# CAN_Breakout_3_0.net
KiCad netlist of a schematic drawn in EAGLE
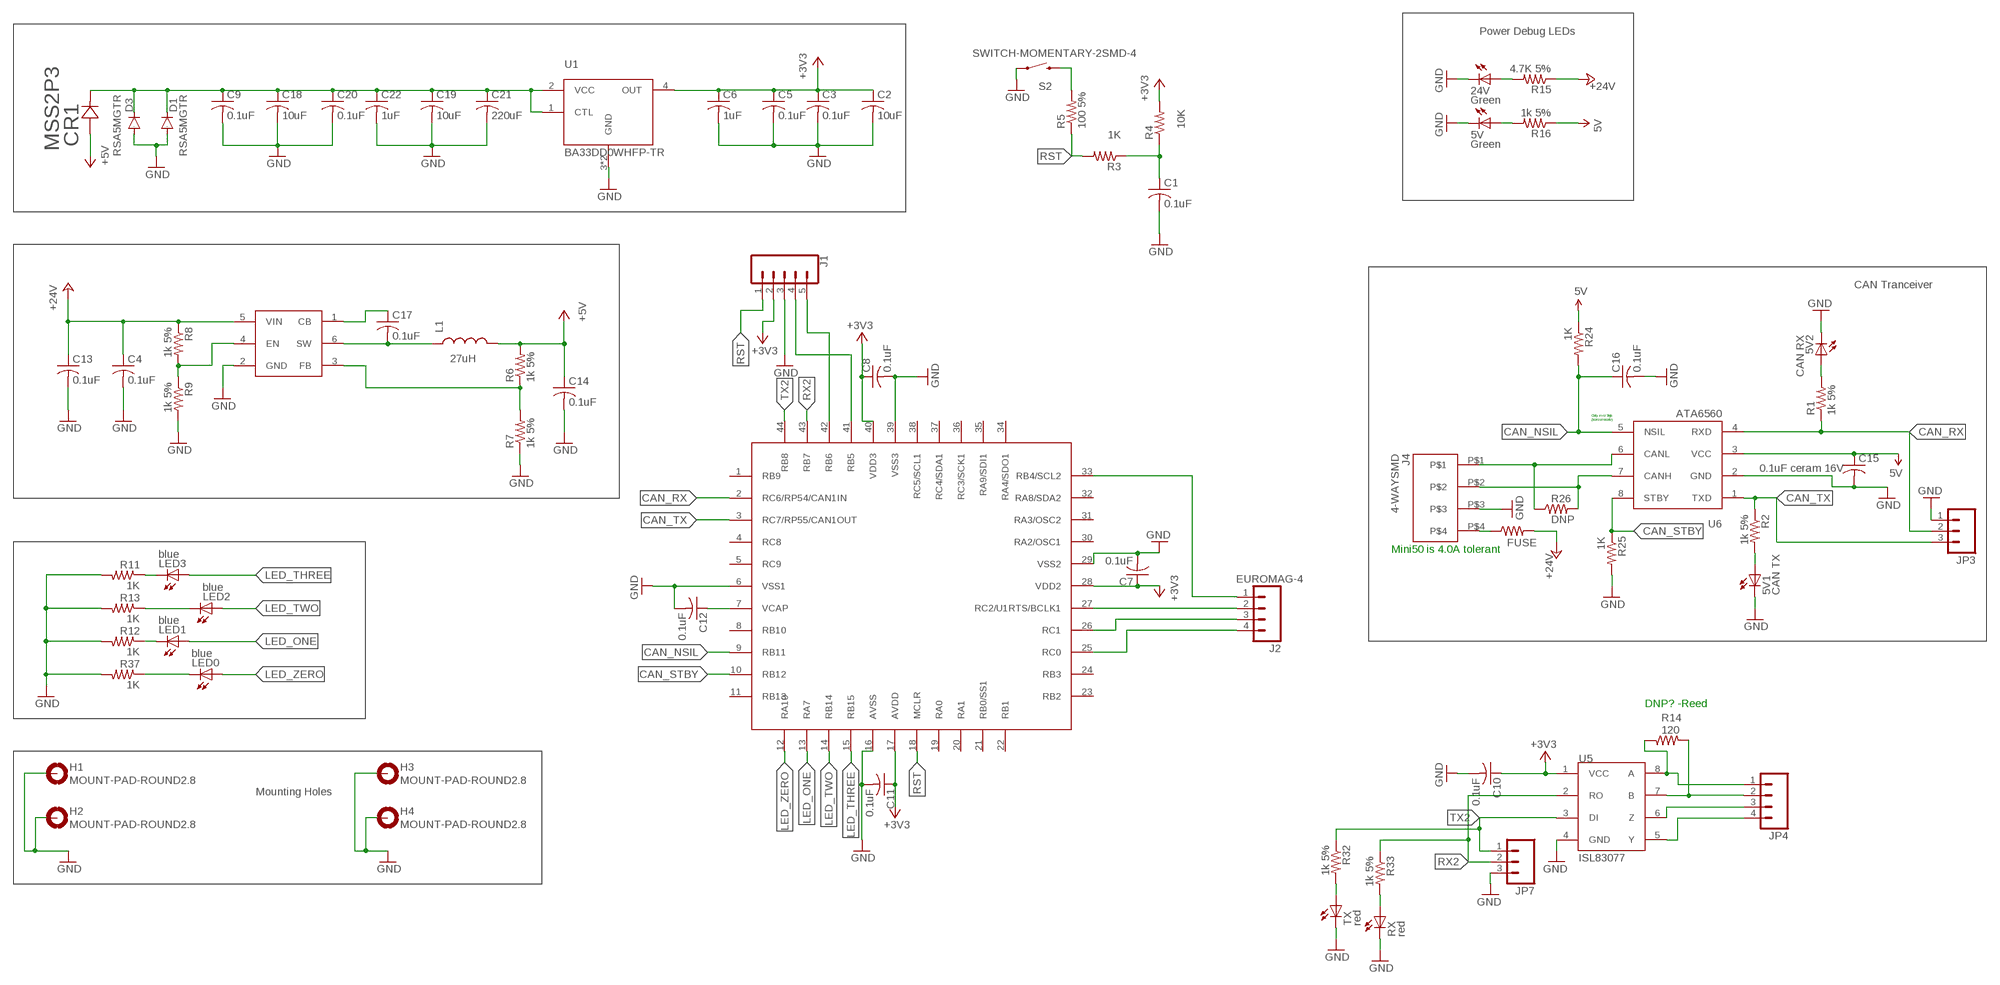
[diagram p0: schematic, sheet 1]

(export (version "E")
  (design (tool "Eeschema 10.0.6"))
  (components
    (comp (ref "5V")
      (value "Green")
      (footprint "eagle-import:CHIP-LED0805")
      (libsource (lib "eagle-import") (part "LEDCHIP-LED0805"))
    )
    (comp (ref "5V1")
      (value "CAN TX")
      (footprint "eagle-import:CHIP-LED0805")
      (libsource (lib "eagle-import") (part "LEDCHIP-LED0805"))
    )
    (comp (ref "5V2")
      (value "CAN RX")
      (footprint "eagle-import:CHIP-LED0805")
      (libsource (lib "eagle-import") (part "LEDCHIP-LED0805"))
    )
    (comp (ref "24V")
      (value "Green")
      (footprint "eagle-import:CHIP-LED0805")
      (libsource (lib "eagle-import") (part "LEDCHIP-LED0805"))
    )
    (comp (ref "C1")
      (value "0.1uF")
      (footprint "eagle-import:C0805")
      (libsource (lib "eagle-import") (part "C-USC0805"))
    )
    (comp (ref "C2")
      (value "10uF")
      (footprint "eagle-import:C0805")
      (libsource (lib "eagle-import") (part "C-USC0805"))
    )
    (comp (ref "C3")
      (value "0.1uF")
      (footprint "eagle-import:C0805")
      (libsource (lib "eagle-import") (part "C-USC0805"))
    )
    (comp (ref "C4")
      (value "0.1uF")
      (footprint "eagle-import:C0805")
      (libsource (lib "eagle-import") (part "C-USC0805"))
    )
    (comp (ref "C5")
      (value "0.1uF")
      (footprint "eagle-import:C0805")
      (libsource (lib "eagle-import") (part "C-USC0805"))
    )
    (comp (ref "C6")
      (value "1uF")
      (footprint "eagle-import:C0805")
      (libsource (lib "eagle-import") (part "C-USC0805"))
    )
    (comp (ref "C7")
      (value "0.1uF")
      (footprint "eagle-import:C0805")
      (libsource (lib "eagle-import") (part "C-USC0805"))
    )
    (comp (ref "C8")
      (value "0.1uF")
      (footprint "eagle-import:C0805")
      (libsource (lib "eagle-import") (part "C-USC0805"))
    )
    (comp (ref "C9")
      (value "0.1uF")
      (footprint "eagle-import:C0805")
      (libsource (lib "eagle-import") (part "C-USC0805"))
    )
    (comp (ref "C10")
      (value "0.1uF")
      (footprint "eagle-import:C0805")
      (libsource (lib "eagle-import") (part "C-USC0805"))
    )
    (comp (ref "C11")
      (value "0.1uF")
      (footprint "eagle-import:C0805")
      (libsource (lib "eagle-import") (part "C-USC0805"))
    )
    (comp (ref "C12")
      (value "0.1uF")
      (footprint "eagle-import:C0805")
      (libsource (lib "eagle-import") (part "C-USC0805"))
    )
    (comp (ref "C13")
      (value "0.1uF")
      (footprint "eagle-import:C0805")
      (libsource (lib "eagle-import") (part "C-USC0805"))
    )
    (comp (ref "C14")
      (value "0.1uF")
      (footprint "eagle-import:C0805")
      (libsource (lib "eagle-import") (part "C-USC0805"))
    )
    (comp (ref "C15")
      (value "0.1uF ceram 16V")
      (footprint "eagle-import:C0805")
      (libsource (lib "eagle-import") (part "C-USC0805"))
    )
    (comp (ref "C16")
      (value "0.1uF")
      (footprint "eagle-import:C0805")
      (libsource (lib "eagle-import") (part "C-USC0805"))
    )
    (comp (ref "C17")
      (value "0.1uF")
      (footprint "eagle-import:C0805")
      (libsource (lib "eagle-import") (part "C-USC0805"))
    )
    (comp (ref "C18")
      (value "10uF")
      (footprint "eagle-import:C0805")
      (libsource (lib "eagle-import") (part "C-USC0805"))
    )
    (comp (ref "C19")
      (value "10uF")
      (footprint "eagle-import:C0805")
      (libsource (lib "eagle-import") (part "C-USC0805"))
    )
    (comp (ref "C20")
      (value "0.1uF")
      (footprint "eagle-import:C0805")
      (libsource (lib "eagle-import") (part "C-USC0805"))
    )
    (comp (ref "C21")
      (value "220uF")
      (footprint "eagle-import:C0805")
      (libsource (lib "eagle-import") (part "C-USC0805"))
    )
    (comp (ref "C22")
      (value "1uF")
      (footprint "eagle-import:C0805")
      (libsource (lib "eagle-import") (part "C-USC0805"))
    )
    (comp (ref "CR1")
      (value "MSS2P3")
      (footprint "eagle-import:DIODE_MSP3V3-L")
      (fields (field (name "MANUFACTURER_PART_NUMBER") "MSS2P3M389A"))
      (libsource (lib "eagle-import") (part "MSS2P3-M3/89ADIODE_MSP3V3-L"))
    )
    (comp (ref "D1")
      (value "RSA5MGTR")
      (footprint "eagle-import:SOD-123_MINI-SMA")
      (libsource (lib "eagle-import") (part "CGRM400-G4"))
    )
    (comp (ref "D3")
      (value "RSA5MGTR")
      (footprint "eagle-import:SOD-123_MINI-SMA")
      (libsource (lib "eagle-import") (part "CGRM400-G4"))
    )
    (comp (ref "FUSE")
      (value "RESISTOR1206")
      (footprint "eagle-import:1206")
      (libsource (lib "eagle-import") (part "RESISTOR1206"))
    )
    (comp (ref "H1")
      (value "MOUNT-PAD-ROUND2.8")
      (footprint "eagle-import:2,8-PAD")
      (libsource (lib "eagle-import") (part "MOUNT-PAD-ROUND2.8"))
    )
    (comp (ref "H2")
      (value "MOUNT-PAD-ROUND2.8")
      (footprint "eagle-import:2,8-PAD")
      (libsource (lib "eagle-import") (part "MOUNT-PAD-ROUND2.8"))
    )
    (comp (ref "H3")
      (value "MOUNT-PAD-ROUND2.8")
      (footprint "eagle-import:2,8-PAD")
      (libsource (lib "eagle-import") (part "MOUNT-PAD-ROUND2.8"))
    )
    (comp (ref "H4")
      (value "MOUNT-PAD-ROUND2.8")
      (footprint "eagle-import:2,8-PAD")
      (libsource (lib "eagle-import") (part "MOUNT-PAD-ROUND2.8"))
    )
    (comp (ref "J1")
      (value "CONN_05")
      (footprint "eagle-import:1X05")
      (libsource (lib "eagle-import") (part "CONN_05"))
    )
    (comp (ref "J2")
      (value "EUROMAG-4")
      (footprint "eagle-import:M4")
      (libsource (lib "eagle-import") (part "EUROMAG-4"))
    )
    (comp (ref "J4")
      (value "4-WAYSMD")
      (footprint "eagle-import:4-WAY-SMD-90D")
      (libsource (lib "eagle-import") (part "4-WAYSMD"))
    )
    (comp (ref "JP3")
      (value "M03LOCK")
      (footprint "eagle-import:1X03_LOCK")
      (libsource (lib "eagle-import") (part "M03LOCK"))
    )
    (comp (ref "JP4")
      (value "M04POLAR_LOCK")
      (footprint "eagle-import:MOLEX-1X4_LOCK")
      (libsource (lib "eagle-import") (part "M04POLAR_LOCK"))
    )
    (comp (ref "JP7")
      (value "M03LOCK")
      (footprint "eagle-import:1X03_LOCK")
      (libsource (lib "eagle-import") (part "M03LOCK"))
    )
    (comp (ref "L1")
      (value "27uH")
      (footprint "eagle-import:0805")
      (libsource (lib "eagle-import") (part "INDUCTOR1"))
    )
    (comp (ref "LED0")
      (value "blue")
      (footprint "eagle-import:CHIPLED_0805")
      (libsource (lib "eagle-import") (part "LEDCHIPLED_0805"))
    )
    (comp (ref "LED1")
      (value "blue")
      (footprint "eagle-import:CHIPLED_0805")
      (libsource (lib "eagle-import") (part "LEDCHIPLED_0805"))
    )
    (comp (ref "LED2")
      (value "blue")
      (footprint "eagle-import:CHIPLED_0805")
      (libsource (lib "eagle-import") (part "LEDCHIPLED_0805"))
    )
    (comp (ref "LED3")
      (value "blue")
      (footprint "eagle-import:CHIPLED_0805")
      (libsource (lib "eagle-import") (part "LEDCHIPLED_0805"))
    )
    (comp (ref "R1")
      (value "1k 5%")
      (footprint "eagle-import:M0805")
      (libsource (lib "eagle-import") (part "R-US_M0805"))
    )
    (comp (ref "R2")
      (value "1k 5%")
      (footprint "eagle-import:M0805")
      (libsource (lib "eagle-import") (part "R-US_M0805"))
    )
    (comp (ref "R3")
      (value "1K")
      (footprint "eagle-import:M0805")
      (libsource (lib "eagle-import") (part "R-US_M0805"))
    )
    (comp (ref "R4")
      (value "10K")
      (footprint "eagle-import:M0805")
      (libsource (lib "eagle-import") (part "R-US_M0805"))
    )
    (comp (ref "R5")
      (value "100 5%")
      (footprint "eagle-import:M0805")
      (libsource (lib "eagle-import") (part "R-US_M0805"))
    )
    (comp (ref "R6")
      (value "1k 5%")
      (footprint "eagle-import:M0805")
      (libsource (lib "eagle-import") (part "R-US_M0805"))
    )
    (comp (ref "R7")
      (value "1k 5%")
      (footprint "eagle-import:M0805")
      (libsource (lib "eagle-import") (part "R-US_M0805"))
    )
    (comp (ref "R8")
      (value "1k 5%")
      (footprint "eagle-import:M0805")
      (libsource (lib "eagle-import") (part "R-US_M0805"))
    )
    (comp (ref "R9")
      (value "1k 5%")
      (footprint "eagle-import:M0805")
      (libsource (lib "eagle-import") (part "R-US_M0805"))
    )
    (comp (ref "R11")
      (value "1K")
      (footprint "eagle-import:M0805")
      (libsource (lib "eagle-import") (part "R-US_M0805"))
    )
    (comp (ref "R12")
      (value "1K")
      (footprint "eagle-import:M0805")
      (libsource (lib "eagle-import") (part "R-US_M0805"))
    )
    (comp (ref "R13")
      (value "1K")
      (footprint "eagle-import:M0805")
      (libsource (lib "eagle-import") (part "R-US_M0805"))
    )
    (comp (ref "R14")
      (value "120")
      (footprint "eagle-import:M0805")
      (libsource (lib "eagle-import") (part "R-US_M0805"))
    )
    (comp (ref "R15")
      (value "4.7K 5%")
      (footprint "eagle-import:M0805")
      (libsource (lib "eagle-import") (part "R-US_M0805"))
    )
    (comp (ref "R16")
      (value "1k 5%")
      (footprint "eagle-import:M0805")
      (libsource (lib "eagle-import") (part "R-US_M0805"))
    )
    (comp (ref "R24")
      (value "1K")
      (footprint "eagle-import:M0805")
      (libsource (lib "eagle-import") (part "R-US_M0805"))
    )
    (comp (ref "R25")
      (value "1K")
      (footprint "eagle-import:M0805")
      (libsource (lib "eagle-import") (part "R-US_M0805"))
    )
    (comp (ref "R26")
      (value "DNP")
      (footprint "eagle-import:M0805")
      (libsource (lib "eagle-import") (part "R-US_M0805"))
    )
    (comp (ref "R32")
      (value "1k 5%")
      (footprint "eagle-import:M0805")
      (libsource (lib "eagle-import") (part "R-US_M0805"))
    )
    (comp (ref "R33")
      (value "1k 5%")
      (footprint "eagle-import:M0805")
      (libsource (lib "eagle-import") (part "R-US_M0805"))
    )
    (comp (ref "R37")
      (value "1K")
      (footprint "eagle-import:M0805")
      (libsource (lib "eagle-import") (part "R-US_M0805"))
    )
    (comp (ref "RX")
      (value "red")
      (footprint "eagle-import:CHIP-LED0805")
      (libsource (lib "eagle-import") (part "LEDCHIP-LED0805"))
    )
    (comp (ref "S2")
      (value "SWITCH-MOMENTARY-2SMD-4")
      (footprint "eagle-import:TACTILE_SWITCH_TALL")
      (libsource (lib "eagle-import") (part "SWITCH-MOMENTARY-2SMD-4"))
    )
    (comp (ref "TX")
      (value "red")
      (footprint "eagle-import:CHIP-LED0805")
      (libsource (lib "eagle-import") (part "LEDCHIP-LED0805"))
    )
    (comp (ref "U1")
      (value "BA33DD0WHFP-TR")
      (footprint "eagle-import:HRP5")
      (libsource (lib "eagle-import") (part "BA33DD0WHFP-TR"))
    )
    (comp (ref "U2")
      (value "DSPIC33EP512GP504")
      (footprint "eagle-import:TQFP-44")
      (libsource (lib "eagle-import") (part "DSPIC33EP512GP504"))
    )
    (comp (ref "U5")
      (value "ISL83077")
      (footprint "eagle-import:SO08")
      (libsource (lib "eagle-import") (part "ISL83077"))
    )
    (comp (ref "U6")
      (value "ATA6560")
      (footprint "eagle-import:SOIC8")
      (libsource (lib "eagle-import") (part "ATA6560"))
    )
    (comp (ref "U7")
      (value "TPS560430YDBVR")
      (footprint "eagle-import:SOT23-6")
      (libsource (lib "eagle-import") (part "TPS560430YDBVR"))
    )
  )
  (nets
    (net (code "1") (name "+3V3") (class "Default")
      (node (ref "C10") (pin "1") (pinfunction "1_1") (pintype "passive"))
      (node (ref "C11") (pin "1") (pinfunction "1_1") (pintype "passive"))
      (node (ref "C2") (pin "1") (pinfunction "1_1") (pintype "passive"))
      (node (ref "C3") (pin "1") (pinfunction "1_1") (pintype "passive"))
      (node (ref "C5") (pin "1") (pinfunction "1_1") (pintype "passive"))
      (node (ref "C6") (pin "1") (pinfunction "1_1") (pintype "passive"))
      (node (ref "C7") (pin "1") (pinfunction "1_1") (pintype "passive"))
      (node (ref "C8") (pin "1") (pinfunction "1_1") (pintype "passive"))
      (node (ref "J1") (pin "2") (pinfunction "2_2") (pintype "passive"))
      (node (ref "R4") (pin "2") (pinfunction "2_2") (pintype "passive"))
      (node (ref "U1") (pin "4") (pinfunction "OUT_4") (pintype "bidirectional"))
      (node (ref "U2") (pin "17") (pinfunction "AVDD_17") (pintype "power_in"))
      (node (ref "U2") (pin "28") (pinfunction "VDD2_28") (pintype "power_in"))
      (node (ref "U2") (pin "40") (pinfunction "VDD3_40") (pintype "power_in"))
      (node (ref "U5") (pin "1") (pinfunction "VCC_1") (pintype "bidirectional"))
    )
    (net (code "2") (name "+5V") (class "Default")
      (node (ref "C14") (pin "1") (pinfunction "1_1") (pintype "passive"))
      (node (ref "CR1") (pin "2") (pinfunction "2_2") (pintype "passive"))
      (node (ref "L1") (pin "2") (pinfunction "2_2") (pintype "passive"))
      (node (ref "R6") (pin "2") (pinfunction "2_2") (pintype "passive"))
    )
    (net (code "3") (name "+24V") (class "Default")
      (node (ref "C13") (pin "1") (pinfunction "1_1") (pintype "passive"))
      (node (ref "C4") (pin "1") (pinfunction "1_1") (pintype "passive"))
      (node (ref "FUSE") (pin "2") (pinfunction "2_2") (pintype "passive"))
      (node (ref "R15") (pin "1") (pinfunction "1_1") (pintype "passive"))
      (node (ref "R8") (pin "1") (pinfunction "1_1") (pintype "passive"))
      (node (ref "U7") (pin "5") (pinfunction "VIN_5") (pintype "bidirectional"))
    )
    (net (code "4") (name "5V") (class "Default")
      (node (ref "C15") (pin "1") (pinfunction "1_1") (pintype "passive"))
      (node (ref "R16") (pin "1") (pinfunction "1_1") (pintype "passive"))
      (node (ref "R24") (pin "1") (pinfunction "1_1") (pintype "passive"))
      (node (ref "U6") (pin "3") (pinfunction "VCC_3") (pintype "power_in"))
    )
    (net (code "5") (name "CAN_NSIL") (class "Default")
      (node (ref "C16") (pin "1") (pinfunction "1_1") (pintype "passive"))
      (node (ref "R24") (pin "2") (pinfunction "2_2") (pintype "passive"))
      (node (ref "U2") (pin "9") (pinfunction "RB11_9") (pintype "bidirectional"))
      (node (ref "U6") (pin "5") (pinfunction "NSIL_5") (pintype "bidirectional"))
    )
    (net (code "6") (name "CAN_RX") (class "Default")
      (node (ref "JP3") (pin "2") (pinfunction "2_2") (pintype "passive"))
      (node (ref "R1") (pin "1") (pinfunction "1_1") (pintype "passive"))
      (node (ref "U2") (pin "2") (pinfunction "RC6/RP54/CAN1IN_2") (pintype "bidirectional"))
      (node (ref "U6") (pin "4") (pinfunction "RXD_4") (pintype "output"))
    )
    (net (code "7") (name "CAN_STBY") (class "Default")
      (node (ref "R25") (pin "1") (pinfunction "1_1") (pintype "passive"))
      (node (ref "U2") (pin "10") (pinfunction "RB12_10") (pintype "bidirectional"))
      (node (ref "U6") (pin "8") (pinfunction "STBY_8") (pintype "input"))
    )
    (net (code "8") (name "CAN_TX") (class "Default")
      (node (ref "JP3") (pin "3") (pinfunction "3_3") (pintype "passive"))
      (node (ref "R2") (pin "1") (pinfunction "1_1") (pintype "passive"))
      (node (ref "U2") (pin "3") (pinfunction "RC7/RP55/CAN1OUT_3") (pintype "bidirectional"))
      (node (ref "U6") (pin "1") (pinfunction "TXD_1") (pintype "output"))
    )
    (net (code "9") (name "GND") (class "Default")
      (node (ref "24V") (pin "C") (pinfunction "C_C") (pintype "passive"))
      (node (ref "5V") (pin "C") (pinfunction "C_C") (pintype "passive"))
      (node (ref "5V1") (pin "C") (pinfunction "C_C") (pintype "passive"))
      (node (ref "5V2") (pin "C") (pinfunction "C_C") (pintype "passive"))
      (node (ref "C1") (pin "2") (pinfunction "2_2") (pintype "passive"))
      (node (ref "C10") (pin "2") (pinfunction "2_2") (pintype "passive"))
      (node (ref "C11") (pin "2") (pinfunction "2_2") (pintype "passive"))
      (node (ref "C12") (pin "2") (pinfunction "2_2") (pintype "passive"))
      (node (ref "C13") (pin "2") (pinfunction "2_2") (pintype "passive"))
      (node (ref "C14") (pin "2") (pinfunction "2_2") (pintype "passive"))
      (node (ref "C15") (pin "2") (pinfunction "2_2") (pintype "passive"))
      (node (ref "C16") (pin "2") (pinfunction "2_2") (pintype "passive"))
      (node (ref "C18") (pin "2") (pinfunction "2_2") (pintype "passive"))
      (node (ref "C19") (pin "2") (pinfunction "2_2") (pintype "passive"))
      (node (ref "C2") (pin "2") (pinfunction "2_2") (pintype "passive"))
      (node (ref "C20") (pin "2") (pinfunction "2_2") (pintype "passive"))
      (node (ref "C21") (pin "2") (pinfunction "2_2") (pintype "passive"))
      (node (ref "C22") (pin "2") (pinfunction "2_2") (pintype "passive"))
      (node (ref "C3") (pin "2") (pinfunction "2_2") (pintype "passive"))
      (node (ref "C4") (pin "2") (pinfunction "2_2") (pintype "passive"))
      (node (ref "C5") (pin "2") (pinfunction "2_2") (pintype "passive"))
      (node (ref "C6") (pin "2") (pinfunction "2_2") (pintype "passive"))
      (node (ref "C7") (pin "2") (pinfunction "2_2") (pintype "passive"))
      (node (ref "C8") (pin "2") (pinfunction "2_2") (pintype "passive"))
      (node (ref "C9") (pin "2") (pinfunction "2_2") (pintype "passive"))
      (node (ref "D1") (pin "A") (pinfunction "A_A") (pintype "passive"))
      (node (ref "D3") (pin "A") (pinfunction "A_A") (pintype "passive"))
      (node (ref "H1") (pin "B2,8") (pinfunction "MOUNT_B2,8") (pintype "passive"))
      (node (ref "H2") (pin "B2,8") (pinfunction "MOUNT_B2,8") (pintype "passive"))
      (node (ref "H3") (pin "B2,8") (pinfunction "MOUNT_B2,8") (pintype "passive"))
      (node (ref "H4") (pin "B2,8") (pinfunction "MOUNT_B2,8") (pintype "passive"))
      (node (ref "J1") (pin "3") (pinfunction "3_3") (pintype "passive"))
      (node (ref "J4") (pin "P$3") (pinfunction "P$3_P$3") (pintype "bidirectional"))
      (node (ref "JP3") (pin "1") (pinfunction "1_1") (pintype "passive"))
      (node (ref "JP7") (pin "3") (pinfunction "3_3") (pintype "passive"))
      (node (ref "R11") (pin "2") (pinfunction "2_2") (pintype "passive"))
      (node (ref "R12") (pin "2") (pinfunction "2_2") (pintype "passive"))
      (node (ref "R13") (pin "2") (pinfunction "2_2") (pintype "passive"))
      (node (ref "R25") (pin "2") (pinfunction "2_2") (pintype "passive"))
      (node (ref "R37") (pin "2") (pinfunction "2_2") (pintype "passive"))
      (node (ref "R7") (pin "1") (pinfunction "1_1") (pintype "passive"))
      (node (ref "R9") (pin "2") (pinfunction "2_2") (pintype "passive"))
      (node (ref "RX") (pin "C") (pinfunction "C_C") (pintype "passive"))
      (node (ref "S2") (pin "A2") (pinfunction "1_A2") (pintype "passive"))
      (node (ref "TX") (pin "C") (pinfunction "C_C") (pintype "passive"))
      (node (ref "U1") (pin "3") (pinfunction "GND_3") (pintype "bidirectional"))
      (node (ref "U1") (pin "G") (pinfunction "GND_G") (pintype "bidirectional"))
      (node (ref "U2") (pin "16") (pinfunction "AVSS_16") (pintype "power_in"))
      (node (ref "U2") (pin "29") (pinfunction "VSS2_29") (pintype "power_in"))
      (node (ref "U2") (pin "39") (pinfunction "VSS3_39") (pintype "power_in"))
      (node (ref "U2") (pin "6") (pinfunction "VSS1_6") (pintype "power_in"))
      (node (ref "U5") (pin "4") (pinfunction "GND_4") (pintype "bidirectional"))
      (node (ref "U6") (pin "2") (pinfunction "GND_2") (pintype "power_in"))
      (node (ref "U7") (pin "2") (pinfunction "GND_2") (pintype "bidirectional"))
    )
    (net (code "10") (name "LED_ONE") (class "Default")
      (node (ref "LED1") (pin "A") (pinfunction "A_A") (pintype "passive"))
      (node (ref "U2") (pin "13") (pinfunction "RA7_13") (pintype "bidirectional"))
    )
    (net (code "11") (name "LED_THREE") (class "Default")
      (node (ref "LED3") (pin "A") (pinfunction "A_A") (pintype "passive"))
      (node (ref "U2") (pin "15") (pinfunction "RB15_15") (pintype "bidirectional"))
    )
    (net (code "12") (name "LED_TWO") (class "Default")
      (node (ref "LED2") (pin "A") (pinfunction "A_A") (pintype "passive"))
      (node (ref "U2") (pin "14") (pinfunction "RB14_14") (pintype "bidirectional"))
    )
    (net (code "13") (name "LED_ZERO") (class "Default")
      (node (ref "LED0") (pin "A") (pinfunction "A_A") (pintype "passive"))
      (node (ref "U2") (pin "12") (pinfunction "RA10_12") (pintype "bidirectional"))
    )
    (net (code "14") (name "Net-(5V-PadA)") (class "Default")
      (node (ref "5V") (pin "A") (pinfunction "A_A") (pintype "passive"))
      (node (ref "R16") (pin "2") (pinfunction "2_2") (pintype "passive"))
    )
    (net (code "15") (name "Net-(5V1-PadA)") (class "Default")
      (node (ref "5V1") (pin "A") (pinfunction "A_A") (pintype "passive"))
      (node (ref "R2") (pin "2") (pinfunction "2_2") (pintype "passive"))
    )
    (net (code "16") (name "Net-(5V2-PadA)") (class "Default")
      (node (ref "5V2") (pin "A") (pinfunction "A_A") (pintype "passive"))
      (node (ref "R1") (pin "2") (pinfunction "2_2") (pintype "passive"))
    )
    (net (code "17") (name "Net-(24V-PadA)") (class "Default")
      (node (ref "24V") (pin "A") (pinfunction "A_A") (pintype "passive"))
      (node (ref "R15") (pin "2") (pinfunction "2_2") (pintype "passive"))
    )
    (net (code "18") (name "Net-(C1-Pad1)") (class "Default")
      (node (ref "C1") (pin "1") (pinfunction "1_1") (pintype "passive"))
      (node (ref "R3") (pin "1") (pinfunction "1_1") (pintype "passive"))
      (node (ref "R4") (pin "1") (pinfunction "1_1") (pintype "passive"))
    )
    (net (code "19") (name "Net-(FUSE-Pad1)") (class "Default")
      (node (ref "FUSE") (pin "1") (pinfunction "1_1") (pintype "passive"))
      (node (ref "J4") (pin "P$4") (pinfunction "P$4_P$4") (pintype "bidirectional"))
    )
    (net (code "20") (name "Net-(LED0-PadC)") (class "Default")
      (node (ref "LED0") (pin "C") (pinfunction "C_C") (pintype "passive"))
      (node (ref "R37") (pin "1") (pinfunction "1_1") (pintype "passive"))
    )
    (net (code "21") (name "Net-(LED1-PadC)") (class "Default")
      (node (ref "LED1") (pin "C") (pinfunction "C_C") (pintype "passive"))
      (node (ref "R12") (pin "1") (pinfunction "1_1") (pintype "passive"))
    )
    (net (code "22") (name "Net-(LED2-PadC)") (class "Default")
      (node (ref "LED2") (pin "C") (pinfunction "C_C") (pintype "passive"))
      (node (ref "R13") (pin "1") (pinfunction "1_1") (pintype "passive"))
    )
    (net (code "23") (name "Net-(LED3-PadC)") (class "Default")
      (node (ref "LED3") (pin "C") (pinfunction "C_C") (pintype "passive"))
      (node (ref "R11") (pin "1") (pinfunction "1_1") (pintype "passive"))
    )
    (net (code "24") (name "Net-(R32-Pad2)") (class "Default")
      (node (ref "R32") (pin "2") (pinfunction "2_2") (pintype "passive"))
      (node (ref "TX") (pin "A") (pinfunction "A_A") (pintype "passive"))
    )
    (net (code "25") (name "Net-(R33-Pad2)") (class "Default")
      (node (ref "R33") (pin "2") (pinfunction "2_2") (pintype "passive"))
      (node (ref "RX") (pin "A") (pinfunction "A_A") (pintype "passive"))
    )
    (net (code "26") (name "Net-(S2-2)") (class "Default")
      (node (ref "R5") (pin "2") (pinfunction "2_2") (pintype "passive"))
      (node (ref "S2") (pin "B2") (pinfunction "2_B2") (pintype "passive"))
    )
    (net (code "27") (name "Net-(U1-CTL)") (class "Default")
      (node (ref "C18") (pin "1") (pinfunction "1_1") (pintype "passive"))
      (node (ref "C19") (pin "1") (pinfunction "1_1") (pintype "passive"))
      (node (ref "C20") (pin "1") (pinfunction "1_1") (pintype "passive"))
      (node (ref "C21") (pin "1") (pinfunction "1_1") (pintype "passive"))
      (node (ref "C22") (pin "1") (pinfunction "1_1") (pintype "passive"))
      (node (ref "C9") (pin "1") (pinfunction "1_1") (pintype "passive"))
      (node (ref "CR1") (pin "1") (pinfunction "1_1") (pintype "passive"))
      (node (ref "D1") (pin "C") (pinfunction "C_C") (pintype "passive"))
      (node (ref "D3") (pin "C") (pinfunction "C_C") (pintype "passive"))
      (node (ref "U1") (pin "1") (pinfunction "CTL_1") (pintype "bidirectional"))
      (node (ref "U1") (pin "2") (pinfunction "VCC_2") (pintype "bidirectional"))
    )
    (net (code "28") (name "Net-(U2-RB4{slash}SCL2)") (class "Default")
      (node (ref "J2") (pin "1") (pinfunction "1_1") (pintype "passive"))
      (node (ref "U2") (pin "33") (pinfunction "RB4/SCL2_33") (pintype "bidirectional"))
    )
    (net (code "29") (name "Net-(U2-RB5)") (class "Default")
      (node (ref "J1") (pin "4") (pinfunction "4_4") (pintype "passive"))
      (node (ref "U2") (pin "41") (pinfunction "RB5_41") (pintype "bidirectional"))
    )
    (net (code "30") (name "Net-(U2-RB6)") (class "Default")
      (node (ref "J1") (pin "5") (pinfunction "5_5") (pintype "passive"))
      (node (ref "U2") (pin "42") (pinfunction "RB6_42") (pintype "bidirectional"))
    )
    (net (code "31") (name "Net-(U2-RC0)") (class "Default")
      (node (ref "J2") (pin "4") (pinfunction "4_4") (pintype "passive"))
      (node (ref "U2") (pin "25") (pinfunction "RC0_25") (pintype "bidirectional"))
    )
    (net (code "32") (name "Net-(U2-RC1)") (class "Default")
      (node (ref "J2") (pin "3") (pinfunction "3_3") (pintype "passive"))
      (node (ref "U2") (pin "26") (pinfunction "RC1_26") (pintype "bidirectional"))
    )
    (net (code "33") (name "Net-(U2-RC2{slash}U1RTS{slash}BCLK1)") (class "Default")
      (node (ref "J2") (pin "2") (pinfunction "2_2") (pintype "passive"))
      (node (ref "U2") (pin "27") (pinfunction "RC2/U1RTS/BCLK1_27") (pintype "bidirectional"))
    )
    (net (code "34") (name "Net-(U2-VCAP)") (class "Default")
      (node (ref "C12") (pin "1") (pinfunction "1_1") (pintype "passive"))
      (node (ref "U2") (pin "7") (pinfunction "VCAP_7") (pintype "power_in"))
    )
    (net (code "35") (name "Net-(U5-A)") (class "Default")
      (node (ref "JP4") (pin "1") (pinfunction "1_1") (pintype "passive"))
      (node (ref "R14") (pin "1") (pinfunction "1_1") (pintype "passive"))
      (node (ref "U5") (pin "8") (pinfunction "A_8") (pintype "bidirectional"))
    )
    (net (code "36") (name "Net-(U5-B)") (class "Default")
      (node (ref "JP4") (pin "2") (pinfunction "2_2") (pintype "passive"))
      (node (ref "R14") (pin "2") (pinfunction "2_2") (pintype "passive"))
      (node (ref "U5") (pin "7") (pinfunction "B_7") (pintype "bidirectional"))
    )
    (net (code "37") (name "Net-(U5-Y)") (class "Default")
      (node (ref "JP4") (pin "4") (pinfunction "4_4") (pintype "passive"))
      (node (ref "U5") (pin "5") (pinfunction "Y_5") (pintype "bidirectional"))
    )
    (net (code "38") (name "Net-(U5-Z)") (class "Default")
      (node (ref "JP4") (pin "3") (pinfunction "3_3") (pintype "passive"))
      (node (ref "U5") (pin "6") (pinfunction "Z_6") (pintype "bidirectional"))
    )
    (net (code "39") (name "Net-(U6-CANH)") (class "Default")
      (node (ref "J4") (pin "P$2") (pinfunction "P$2_P$2") (pintype "bidirectional"))
      (node (ref "R26") (pin "2") (pinfunction "2_2") (pintype "passive"))
      (node (ref "U6") (pin "7") (pinfunction "CANH_7") (pintype "bidirectional"))
    )
    (net (code "40") (name "Net-(U6-CANL)") (class "Default")
      (node (ref "J4") (pin "P$1") (pinfunction "P$1_P$1") (pintype "bidirectional"))
      (node (ref "R26") (pin "1") (pinfunction "1_1") (pintype "passive"))
      (node (ref "U6") (pin "6") (pinfunction "CANL_6") (pintype "bidirectional"))
    )
    (net (code "41") (name "Net-(U7-CB)") (class "Default")
      (node (ref "C17") (pin "1") (pinfunction "1_1") (pintype "passive"))
      (node (ref "U7") (pin "1") (pinfunction "CB_1") (pintype "bidirectional"))
    )
    (net (code "42") (name "Net-(U7-EN)") (class "Default")
      (node (ref "R8") (pin "2") (pinfunction "2_2") (pintype "passive"))
      (node (ref "R9") (pin "1") (pinfunction "1_1") (pintype "passive"))
      (node (ref "U7") (pin "4") (pinfunction "EN_4") (pintype "bidirectional"))
    )
    (net (code "43") (name "Net-(U7-FB)") (class "Default")
      (node (ref "R6") (pin "1") (pinfunction "1_1") (pintype "passive"))
      (node (ref "R7") (pin "2") (pinfunction "2_2") (pintype "passive"))
      (node (ref "U7") (pin "3") (pinfunction "FB_3") (pintype "bidirectional"))
    )
    (net (code "44") (name "Net-(U7-SW)") (class "Default")
      (node (ref "C17") (pin "2") (pinfunction "2_2") (pintype "passive"))
      (node (ref "L1") (pin "1") (pinfunction "1_1") (pintype "passive"))
      (node (ref "U7") (pin "6") (pinfunction "SW_6") (pintype "bidirectional"))
    )
    (net (code "45") (name "RST") (class "Default")
      (node (ref "J1") (pin "1") (pinfunction "1_1") (pintype "passive"))
      (node (ref "R3") (pin "2") (pinfunction "2_2") (pintype "passive"))
      (node (ref "R5") (pin "1") (pinfunction "1_1") (pintype "passive"))
      (node (ref "U2") (pin "18") (pinfunction "MCLR_18") (pintype "bidirectional"))
    )
    (net (code "46") (name "RX2") (class "Default")
      (node (ref "JP7") (pin "2") (pinfunction "2_2") (pintype "passive"))
      (node (ref "R33") (pin "1") (pinfunction "1_1") (pintype "passive"))
      (node (ref "U2") (pin "43") (pinfunction "RB7_43") (pintype "bidirectional"))
      (node (ref "U5") (pin "2") (pinfunction "RO_2") (pintype "bidirectional"))
    )
    (net (code "47") (name "TX2") (class "Default")
      (node (ref "JP7") (pin "1") (pinfunction "1_1") (pintype "passive"))
      (node (ref "R32") (pin "1") (pinfunction "1_1") (pintype "passive"))
      (node (ref "U2") (pin "44") (pinfunction "RB8_44") (pintype "bidirectional"))
      (node (ref "U5") (pin "3") (pinfunction "DI_3") (pintype "bidirectional"))
    )
    (net (code "48") (name "unconnected-(U2-RA0-Pad19)") (class "Default")
      (node (ref "U2") (pin "19") (pinfunction "RA0_19") (pintype "bidirectional"))
    )
    (net (code "49") (name "unconnected-(U2-RA1-Pad20)") (class "Default")
      (node (ref "U2") (pin "20") (pinfunction "RA1_20") (pintype "bidirectional"))
    )
    (net (code "50") (name "unconnected-(U2-RA2{slash}OSC1-Pad30)") (class "Default")
      (node (ref "U2") (pin "30") (pinfunction "RA2/OSC1_30") (pintype "bidirectional"))
    )
    (net (code "51") (name "unconnected-(U2-RA3{slash}OSC2-Pad31)") (class "Default")
      (node (ref "U2") (pin "31") (pinfunction "RA3/OSC2_31") (pintype "bidirectional"))
    )
    (net (code "52") (name "unconnected-(U2-RA4{slash}SDO1-Pad34)") (class "Default")
      (node (ref "U2") (pin "34") (pinfunction "RA4/SDO1_34") (pintype "bidirectional"))
    )
    (net (code "53") (name "unconnected-(U2-RA8{slash}SDA2-Pad32)") (class "Default")
      (node (ref "U2") (pin "32") (pinfunction "RA8/SDA2_32") (pintype "bidirectional"))
    )
    (net (code "54") (name "unconnected-(U2-RA9{slash}SDI1-Pad35)") (class "Default")
      (node (ref "U2") (pin "35") (pinfunction "RA9/SDI1_35") (pintype "bidirectional"))
    )
    (net (code "55") (name "unconnected-(U2-RB0{slash}SS1-Pad21)") (class "Default")
      (node (ref "U2") (pin "21") (pinfunction "RB0/SS1_21") (pintype "bidirectional"))
    )
    (net (code "56") (name "unconnected-(U2-RB1-Pad22)") (class "Default")
      (node (ref "U2") (pin "22") (pinfunction "RB1_22") (pintype "bidirectional"))
    )
    (net (code "57") (name "unconnected-(U2-RB2-Pad23)") (class "Default")
      (node (ref "U2") (pin "23") (pinfunction "RB2_23") (pintype "bidirectional"))
    )
    (net (code "58") (name "unconnected-(U2-RB3-Pad24)") (class "Default")
      (node (ref "U2") (pin "24") (pinfunction "RB3_24") (pintype "bidirectional"))
    )
    (net (code "59") (name "unconnected-(U2-RB9-Pad1)") (class "Default")
      (node (ref "U2") (pin "1") (pinfunction "RB9_1") (pintype "bidirectional"))
    )
    (net (code "60") (name "unconnected-(U2-RB10-Pad8)") (class "Default")
      (node (ref "U2") (pin "8") (pinfunction "RB10_8") (pintype "bidirectional"))
    )
    (net (code "61") (name "unconnected-(U2-RB13-Pad11)") (class "Default")
      (node (ref "U2") (pin "11") (pinfunction "RB13_11") (pintype "bidirectional"))
    )
    (net (code "62") (name "unconnected-(U2-RC3{slash}SCK1-Pad36)") (class "Default")
      (node (ref "U2") (pin "36") (pinfunction "RC3/SCK1_36") (pintype "bidirectional"))
    )
    (net (code "63") (name "unconnected-(U2-RC4{slash}SDA1-Pad37)") (class "Default")
      (node (ref "U2") (pin "37") (pinfunction "RC4/SDA1_37") (pintype "bidirectional"))
    )
    (net (code "64") (name "unconnected-(U2-RC5{slash}SCL1-Pad38)") (class "Default")
      (node (ref "U2") (pin "38") (pinfunction "RC5/SCL1_38") (pintype "bidirectional"))
    )
    (net (code "65") (name "unconnected-(U2-RC8-Pad4)") (class "Default")
      (node (ref "U2") (pin "4") (pinfunction "RC8_4") (pintype "bidirectional"))
    )
    (net (code "66") (name "unconnected-(U2-RC9-Pad5)") (class "Default")
      (node (ref "U2") (pin "5") (pinfunction "RC9_5") (pintype "bidirectional"))
    )
  )
)
